# lipo-shutoff.net
KiCad netlist of a schematic drawn in EAGLE
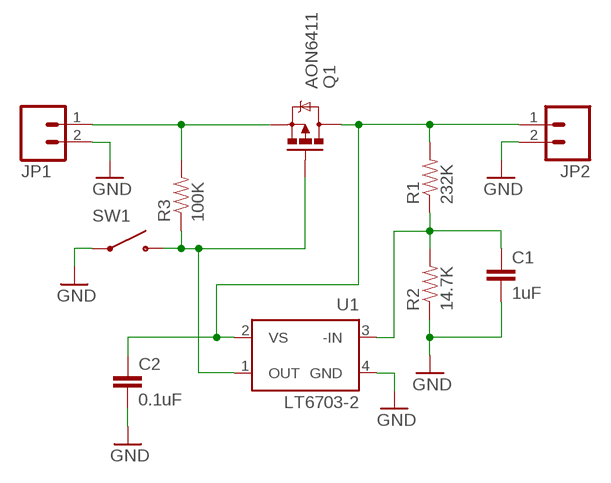
[diagram p0: schematic, sheet 1]

(export (version "E")
  (design (tool "Eeschema 10.0.6"))
  (components
    (comp (ref "C1")
      (value "1uF")
      (footprint "eagle-import:0603-CAP")
      (libsource (lib "eagle-import") (part "CAP0603-CAP"))
    )
    (comp (ref "C2")
      (value "0.1uF")
      (footprint "eagle-import:0603-CAP")
      (libsource (lib "eagle-import") (part "CAP0603-CAP"))
    )
    (comp (ref "JP1")
      (value "M02LOCK_LONGPADS")
      (footprint "eagle-import:1X02_LOCK_LONGPADS")
      (libsource (lib "eagle-import") (part "M02LOCK_LONGPADS"))
    )
    (comp (ref "JP2")
      (value "M02LOCK_LONGPADS")
      (footprint "eagle-import:1X02_LOCK_LONGPADS")
      (libsource (lib "eagle-import") (part "M02LOCK_LONGPADS"))
    )
    (comp (ref "Q1")
      (value "AON6411")
      (footprint "eagle-import:DFN5X6")
      (libsource (lib "eagle-import") (part "AON6411"))
    )
    (comp (ref "R1")
      (value "232K")
      (footprint "eagle-import:0603-RES")
      (libsource (lib "eagle-import") (part "RESISTOR0603-RES"))
    )
    (comp (ref "R2")
      (value "14.7K")
      (footprint "eagle-import:0603-RES")
      (libsource (lib "eagle-import") (part "RESISTOR0603-RES"))
    )
    (comp (ref "R3")
      (value "100K")
      (footprint "eagle-import:0603-RES")
      (libsource (lib "eagle-import") (part "RESISTOR0603-RES"))
    )
    (comp (ref "SW1")
      (value "FSM4JSMA")
      (footprint "eagle-import:FSM4JSMA")
      (libsource (lib "eagle-import") (part "FSM4JSMA"))
    )
    (comp (ref "U1")
      (value "LT6703-2")
      (footprint "eagle-import:LT6703")
      (libsource (lib "eagle-import") (part "LT6703-2"))
    )
  )
  (nets
    (net (code "1") (name "GND") (class "Default")
      (node (ref "C1") (pin "2") (pinfunction "2_2") (pintype "passive"))
      (node (ref "C2") (pin "2") (pinfunction "2_2") (pintype "passive"))
      (node (ref "JP1") (pin "2") (pinfunction "2_2") (pintype "passive"))
      (node (ref "JP2") (pin "2") (pinfunction "2_2") (pintype "passive"))
      (node (ref "R2") (pin "1") (pinfunction "1_1") (pintype "passive"))
      (node (ref "SW1") (pin "1") (pinfunction "1_1") (pintype "bidirectional"))
      (node (ref "SW1") (pin "2") (pinfunction "1_2") (pintype "bidirectional"))
      (node (ref "U1") (pin "4") (pinfunction "GND_4") (pintype "bidirectional"))
    )
    (net (code "2") (name "Net-(JP1-Pad1)") (class "Default")
      (node (ref "JP1") (pin "1") (pinfunction "1_1") (pintype "passive"))
      (node (ref "Q1") (pin "1") (pinfunction "S_1") (pintype "passive"))
      (node (ref "Q1") (pin "2") (pinfunction "S_2") (pintype "passive"))
      (node (ref "Q1") (pin "3") (pinfunction "S_3") (pintype "passive"))
      (node (ref "R3") (pin "2") (pinfunction "2_2") (pintype "passive"))
    )
    (net (code "3") (name "Net-(Q1-G)") (class "Default")
      (node (ref "Q1") (pin "4") (pinfunction "G_4") (pintype "passive"))
      (node (ref "R3") (pin "1") (pinfunction "1_1") (pintype "passive"))
      (node (ref "SW1") (pin "3") (pinfunction "2_3") (pintype "bidirectional"))
      (node (ref "SW1") (pin "4") (pinfunction "2_4") (pintype "bidirectional"))
      (node (ref "U1") (pin "1") (pinfunction "OUT_1") (pintype "bidirectional"))
    )
    (net (code "4") (name "Net-(U1--IN)") (class "Default")
      (node (ref "C1") (pin "1") (pinfunction "1_1") (pintype "passive"))
      (node (ref "R1") (pin "1") (pinfunction "1_1") (pintype "passive"))
      (node (ref "R2") (pin "2") (pinfunction "2_2") (pintype "passive"))
      (node (ref "U1") (pin "3") (pinfunction "-IN_3") (pintype "bidirectional"))
    )
    (net (code "5") (name "Net-(U1-VS)") (class "Default")
      (node (ref "C2") (pin "1") (pinfunction "1_1") (pintype "passive"))
      (node (ref "JP2") (pin "1") (pinfunction "1_1") (pintype "passive"))
      (node (ref "Q1") (pin "5") (pinfunction "D_5") (pintype "passive"))
      (node (ref "Q1") (pin "6") (pinfunction "D_6") (pintype "passive"))
      (node (ref "Q1") (pin "7") (pinfunction "D_7") (pintype "passive"))
      (node (ref "Q1") (pin "8") (pinfunction "D_8") (pintype "passive"))
      (node (ref "Q1") (pin "PAD") (pinfunction "D_PAD") (pintype "passive"))
      (node (ref "R1") (pin "2") (pinfunction "2_2") (pintype "passive"))
      (node (ref "U1") (pin "2") (pinfunction "VS_2") (pintype "bidirectional"))
    )
  )
)
